# servo_driver_board.net
KiCad netlist of a schematic drawn in EAGLE
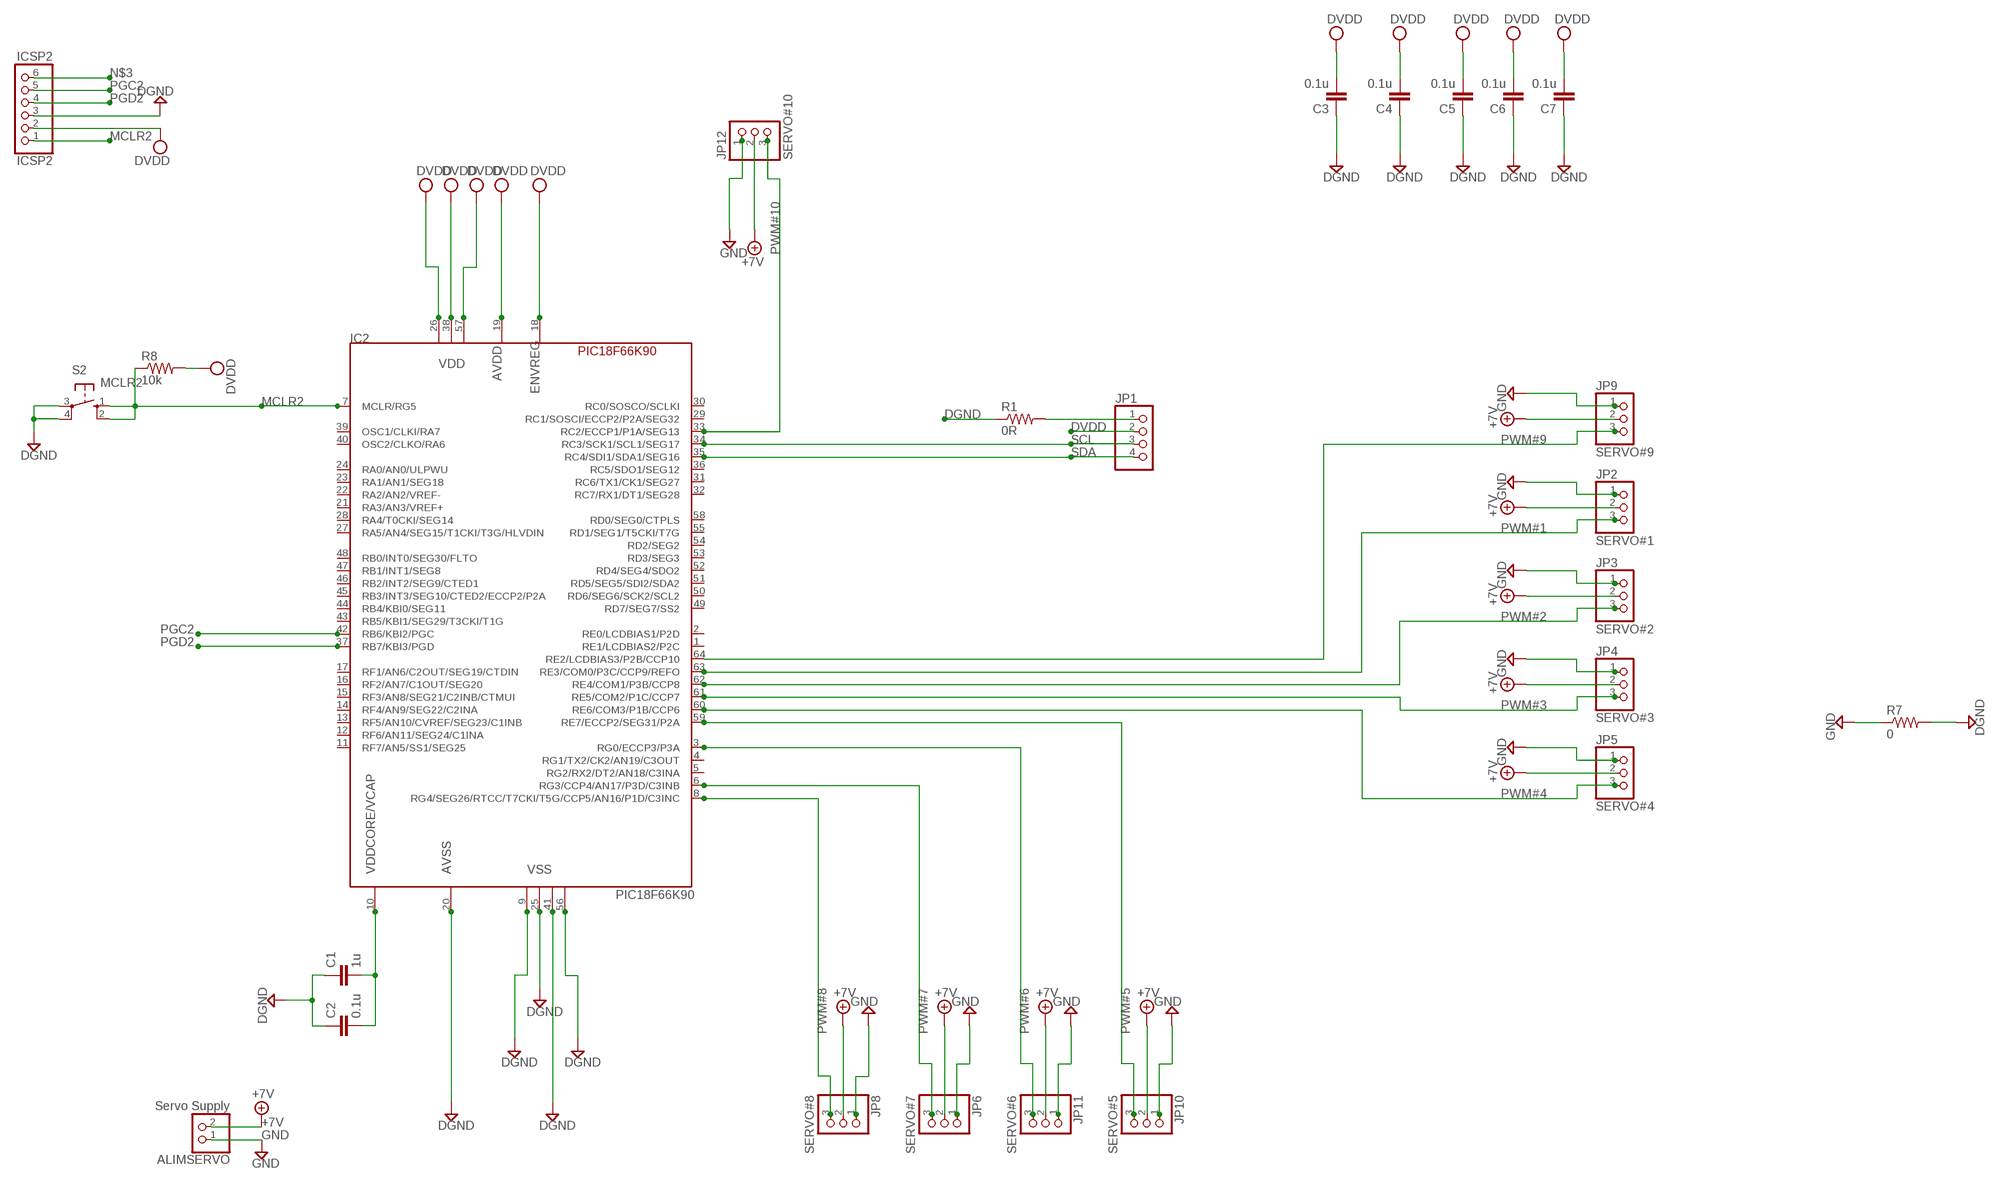
[diagram p0: schematic, sheet 1]

(export (version "E")
  (design (tool "Eeschema 10.0.6"))
  (components
    (comp (ref "ALIMSERVO")
      (value "Servo Supply")
      (footprint "eagle-import:1X02")
      (libsource (lib "eagle-import") (part "PINHD-1X2"))
    )
    (comp (ref "C1")
      (value "1u")
      (footprint "eagle-import:C0805")
      (libsource (lib "eagle-import") (part "C-EUC0805"))
    )
    (comp (ref "C2")
      (value "0.1u")
      (footprint "eagle-import:C0805")
      (libsource (lib "eagle-import") (part "C-EUC0805"))
    )
    (comp (ref "C3")
      (value "0.1u")
      (footprint "eagle-import:C0805")
      (libsource (lib "eagle-import") (part "C-EUC0805"))
    )
    (comp (ref "C4")
      (value "0.1u")
      (footprint "eagle-import:C0805")
      (libsource (lib "eagle-import") (part "C-EUC0805"))
    )
    (comp (ref "C5")
      (value "0.1u")
      (footprint "eagle-import:C0805")
      (libsource (lib "eagle-import") (part "C-EUC0805"))
    )
    (comp (ref "C6")
      (value "0.1u")
      (footprint "eagle-import:C0805")
      (libsource (lib "eagle-import") (part "C-EUC0805"))
    )
    (comp (ref "C7")
      (value "0.1u")
      (footprint "eagle-import:C0805")
      (libsource (lib "eagle-import") (part "C-EUC0805"))
    )
    (comp (ref "IC2")
      (value "PIC18F66K90")
      (footprint "eagle-import:TQFP64-10X10")
      (libsource (lib "eagle-import") (part "PIC18F66K90"))
    )
    (comp (ref "ICSP2")
      (value "ICSP2")
      (footprint "eagle-import:1X06")
      (libsource (lib "eagle-import") (part "PINHD-1X6"))
    )
    (comp (ref "JP1")
      (value "PINHD-1X4/90")
      (footprint "eagle-import:1X04_90")
      (libsource (lib "eagle-import") (part "PINHD-1X4/90"))
    )
    (comp (ref "JP2")
      (value "SERVO#1")
      (footprint "eagle-import:1X03")
      (libsource (lib "eagle-import") (part "PINHD-1X3"))
    )
    (comp (ref "JP3")
      (value "SERVO#2")
      (footprint "eagle-import:1X03")
      (libsource (lib "eagle-import") (part "PINHD-1X3"))
    )
    (comp (ref "JP4")
      (value "SERVO#3")
      (footprint "eagle-import:1X03")
      (libsource (lib "eagle-import") (part "PINHD-1X3"))
    )
    (comp (ref "JP5")
      (value "SERVO#4")
      (footprint "eagle-import:1X03")
      (libsource (lib "eagle-import") (part "PINHD-1X3"))
    )
    (comp (ref "JP6")
      (value "SERVO#7")
      (footprint "eagle-import:1X03")
      (libsource (lib "eagle-import") (part "PINHD-1X3"))
    )
    (comp (ref "JP8")
      (value "SERVO#8")
      (footprint "eagle-import:1X03")
      (libsource (lib "eagle-import") (part "PINHD-1X3"))
    )
    (comp (ref "JP9")
      (value "SERVO#9")
      (footprint "eagle-import:1X03")
      (libsource (lib "eagle-import") (part "PINHD-1X3"))
    )
    (comp (ref "JP10")
      (value "SERVO#5")
      (footprint "eagle-import:1X03")
      (libsource (lib "eagle-import") (part "PINHD-1X3"))
    )
    (comp (ref "JP11")
      (value "SERVO#6")
      (footprint "eagle-import:1X03")
      (libsource (lib "eagle-import") (part "PINHD-1X3"))
    )
    (comp (ref "JP12")
      (value "SERVO#10")
      (footprint "eagle-import:1X03")
      (libsource (lib "eagle-import") (part "PINHD-1X3"))
    )
    (comp (ref "R1")
      (value "0R")
      (footprint "eagle-import:R1206")
      (libsource (lib "eagle-import") (part "R-US_R1206"))
    )
    (comp (ref "R7")
      (value "0")
      (footprint "eagle-import:R1206")
      (libsource (lib "eagle-import") (part "R-US_R1206"))
    )
    (comp (ref "R8")
      (value "10k")
      (footprint "eagle-import:R1206")
      (libsource (lib "eagle-import") (part "R-US_R1206"))
    )
    (comp (ref "S2")
      (value "MCLR2")
      (footprint "eagle-import:B3F-10XX")
      (fields (field (name "MPN") "B3F-1000"))
      (libsource (lib "eagle-import") (part "10-XX"))
    )
  )
  (nets
    (net (code "1") (name "+7V") (class "Default")
      (node (ref "ALIMSERVO") (pin "2") (pinfunction "2_2") (pintype "passive"))
      (node (ref "JP10") (pin "2") (pinfunction "2_2") (pintype "passive"))
      (node (ref "JP11") (pin "2") (pinfunction "2_2") (pintype "passive"))
      (node (ref "JP12") (pin "2") (pinfunction "2_2") (pintype "passive"))
      (node (ref "JP2") (pin "2") (pinfunction "2_2") (pintype "passive"))
      (node (ref "JP3") (pin "2") (pinfunction "2_2") (pintype "passive"))
      (node (ref "JP4") (pin "2") (pinfunction "2_2") (pintype "passive"))
      (node (ref "JP5") (pin "2") (pinfunction "2_2") (pintype "passive"))
      (node (ref "JP6") (pin "2") (pinfunction "2_2") (pintype "passive"))
      (node (ref "JP8") (pin "2") (pinfunction "2_2") (pintype "passive"))
      (node (ref "JP9") (pin "2") (pinfunction "2_2") (pintype "passive"))
    )
    (net (code "2") (name "/MCLR2") (class "Default")
      (node (ref "IC2") (pin "7") (pinfunction "MCLR/RG5_7") (pintype "input"))
      (node (ref "ICSP2") (pin "1") (pinfunction "1_1") (pintype "passive"))
      (node (ref "R8") (pin "1") (pinfunction "1_1") (pintype "passive"))
      (node (ref "S2") (pin "1") (pinfunction "S_1") (pintype "passive"))
      (node (ref "S2") (pin "2") (pinfunction "S1_2") (pintype "passive"))
    )
    (net (code "3") (name "/N$3") (class "Default")
      (node (ref "ICSP2") (pin "6") (pinfunction "6_6") (pintype "passive"))
    )
    (net (code "4") (name "/PGC2") (class "Default")
      (node (ref "IC2") (pin "42") (pinfunction "RB6/KBI2/PGC_42") (pintype "bidirectional"))
      (node (ref "ICSP2") (pin "5") (pinfunction "5_5") (pintype "passive"))
    )
    (net (code "5") (name "/PGD2") (class "Default")
      (node (ref "IC2") (pin "37") (pinfunction "RB7/KBI3/PGD_37") (pintype "bidirectional"))
      (node (ref "ICSP2") (pin "4") (pinfunction "4_4") (pintype "passive"))
    )
    (net (code "6") (name "/SCL") (class "Default")
      (node (ref "IC2") (pin "34") (pinfunction "RC3/SCK1/SCL1/SEG17_34") (pintype "bidirectional"))
      (node (ref "JP1") (pin "3") (pinfunction "3_3") (pintype "passive"))
    )
    (net (code "7") (name "/SDA") (class "Default")
      (node (ref "IC2") (pin "35") (pinfunction "RC4/SDI1/SDA1/SEG16_35") (pintype "bidirectional"))
      (node (ref "JP1") (pin "4") (pinfunction "4_4") (pintype "passive"))
    )
    (net (code "8") (name "DGND") (class "Default")
      (node (ref "C1") (pin "1") (pinfunction "1_1") (pintype "passive"))
      (node (ref "C2") (pin "1") (pinfunction "1_1") (pintype "passive"))
      (node (ref "C3") (pin "1") (pinfunction "1_1") (pintype "passive"))
      (node (ref "C4") (pin "1") (pinfunction "1_1") (pintype "passive"))
      (node (ref "C5") (pin "1") (pinfunction "1_1") (pintype "passive"))
      (node (ref "C6") (pin "1") (pinfunction "1_1") (pintype "passive"))
      (node (ref "C7") (pin "1") (pinfunction "1_1") (pintype "passive"))
      (node (ref "IC2") (pin "20") (pinfunction "AVSS_20") (pintype "power_in"))
      (node (ref "IC2") (pin "25") (pinfunction "VSS_25") (pintype "power_in"))
      (node (ref "IC2") (pin "41") (pinfunction "VSS_41") (pintype "power_in"))
      (node (ref "IC2") (pin "56") (pinfunction "VSS_56") (pintype "power_in"))
      (node (ref "IC2") (pin "9") (pinfunction "VSS_9") (pintype "power_in"))
      (node (ref "ICSP2") (pin "3") (pinfunction "3_3") (pintype "passive"))
      (node (ref "R1") (pin "1") (pinfunction "1_1") (pintype "passive"))
      (node (ref "R7") (pin "2") (pinfunction "2_2") (pintype "passive"))
      (node (ref "S2") (pin "3") (pinfunction "P_3") (pintype "passive"))
      (node (ref "S2") (pin "4") (pinfunction "P1_4") (pintype "passive"))
    )
    (net (code "9") (name "DVDD") (class "Default")
      (node (ref "C3") (pin "2") (pinfunction "2_2") (pintype "passive"))
      (node (ref "C4") (pin "2") (pinfunction "2_2") (pintype "passive"))
      (node (ref "C5") (pin "2") (pinfunction "2_2") (pintype "passive"))
      (node (ref "C6") (pin "2") (pinfunction "2_2") (pintype "passive"))
      (node (ref "C7") (pin "2") (pinfunction "2_2") (pintype "passive"))
      (node (ref "IC2") (pin "18") (pinfunction "ENVREG_18") (pintype "power_in"))
      (node (ref "IC2") (pin "19") (pinfunction "AVDD_19") (pintype "power_in"))
      (node (ref "IC2") (pin "26") (pinfunction "VDD_26") (pintype "power_in"))
      (node (ref "IC2") (pin "38") (pinfunction "VDD_38") (pintype "power_in"))
      (node (ref "IC2") (pin "57") (pinfunction "VDD_57") (pintype "power_in"))
      (node (ref "ICSP2") (pin "2") (pinfunction "2_2") (pintype "passive"))
      (node (ref "JP1") (pin "2") (pinfunction "2_2") (pintype "passive"))
      (node (ref "R8") (pin "2") (pinfunction "2_2") (pintype "passive"))
    )
    (net (code "10") (name "GND") (class "Default")
      (node (ref "ALIMSERVO") (pin "1") (pinfunction "1_1") (pintype "passive"))
      (node (ref "JP10") (pin "1") (pinfunction "1_1") (pintype "passive"))
      (node (ref "JP11") (pin "1") (pinfunction "1_1") (pintype "passive"))
      (node (ref "JP12") (pin "1") (pinfunction "1_1") (pintype "passive"))
      (node (ref "JP2") (pin "1") (pinfunction "1_1") (pintype "passive"))
      (node (ref "JP3") (pin "1") (pinfunction "1_1") (pintype "passive"))
      (node (ref "JP4") (pin "1") (pinfunction "1_1") (pintype "passive"))
      (node (ref "JP5") (pin "1") (pinfunction "1_1") (pintype "passive"))
      (node (ref "JP6") (pin "1") (pinfunction "1_1") (pintype "passive"))
      (node (ref "JP8") (pin "1") (pinfunction "1_1") (pintype "passive"))
      (node (ref "JP9") (pin "1") (pinfunction "1_1") (pintype "passive"))
      (node (ref "R7") (pin "1") (pinfunction "1_1") (pintype "passive"))
    )
    (net (code "11") (name "Net-(IC2-RC2{slash}ECCP1{slash}P1A{slash}SEG13)") (class "Default")
      (node (ref "IC2") (pin "33") (pinfunction "RC2/ECCP1/P1A/SEG13_33") (pintype "bidirectional"))
      (node (ref "JP12") (pin "3") (pinfunction "3_3") (pintype "passive"))
    )
    (net (code "12") (name "Net-(IC2-RE2{slash}LCDBIAS3{slash}P2B{slash}CCP10)") (class "Default")
      (node (ref "IC2") (pin "64") (pinfunction "RE2/LCDBIAS3/P2B/CCP10_64") (pintype "bidirectional"))
      (node (ref "JP9") (pin "3") (pinfunction "3_3") (pintype "passive"))
    )
    (net (code "13") (name "Net-(IC2-RE3{slash}COM0{slash}P3C{slash}CCP9{slash}REFO)") (class "Default")
      (node (ref "IC2") (pin "63") (pinfunction "RE3/COM0/P3C/CCP9/REFO_63") (pintype "bidirectional"))
      (node (ref "JP2") (pin "3") (pinfunction "3_3") (pintype "passive"))
    )
    (net (code "14") (name "Net-(IC2-RE4{slash}COM1{slash}P3B{slash}CCP8)") (class "Default")
      (node (ref "IC2") (pin "62") (pinfunction "RE4/COM1/P3B/CCP8_62") (pintype "bidirectional"))
      (node (ref "JP3") (pin "3") (pinfunction "3_3") (pintype "passive"))
    )
    (net (code "15") (name "Net-(IC2-RE5{slash}COM2{slash}P1C{slash}CCP7)") (class "Default")
      (node (ref "IC2") (pin "61") (pinfunction "RE5/COM2/P1C/CCP7_61") (pintype "bidirectional"))
      (node (ref "JP4") (pin "3") (pinfunction "3_3") (pintype "passive"))
    )
    (net (code "16") (name "Net-(IC2-RE6{slash}COM3{slash}P1B{slash}CCP6)") (class "Default")
      (node (ref "IC2") (pin "60") (pinfunction "RE6/COM3/P1B/CCP6_60") (pintype "bidirectional"))
      (node (ref "JP5") (pin "3") (pinfunction "3_3") (pintype "passive"))
    )
    (net (code "17") (name "Net-(IC2-RE7{slash}ECCP2{slash}SEG31{slash}P2A)") (class "Default")
      (node (ref "IC2") (pin "59") (pinfunction "RE7/ECCP2/SEG31/P2A_59") (pintype "bidirectional"))
      (node (ref "JP10") (pin "3") (pinfunction "3_3") (pintype "passive"))
    )
    (net (code "18") (name "Net-(IC2-RG0{slash}ECCP3{slash}P3A)") (class "Default")
      (node (ref "IC2") (pin "3") (pinfunction "RG0/ECCP3/P3A_3") (pintype "bidirectional"))
      (node (ref "JP11") (pin "3") (pinfunction "3_3") (pintype "passive"))
    )
    (net (code "19") (name "Net-(IC2-RG3{slash}CCP4{slash}AN17{slash}P3D{slash}C3INB)") (class "Default")
      (node (ref "IC2") (pin "6") (pinfunction "RG3/CCP4/AN17/P3D/C3INB_6") (pintype "bidirectional"))
      (node (ref "JP6") (pin "3") (pinfunction "3_3") (pintype "passive"))
    )
    (net (code "20") (name "Net-(IC2-RG4{slash}SEG26{slash}RTCC{slash}T7CKI{slash}T5G{slash}CCP5{slash}AN16{slash}P1D{slash}C3INC)") (class "Default")
      (node (ref "IC2") (pin "8") (pinfunction "RG4/SEG26/RTCC/T7CKI/T5G/CCP5/AN16/P1D/C3INC_8") (pintype "bidirectional"))
      (node (ref "JP8") (pin "3") (pinfunction "3_3") (pintype "passive"))
    )
    (net (code "21") (name "Net-(IC2-VDDCORE{slash}VCAP)") (class "Default")
      (node (ref "C1") (pin "2") (pinfunction "2_2") (pintype "passive"))
      (node (ref "C2") (pin "2") (pinfunction "2_2") (pintype "passive"))
      (node (ref "IC2") (pin "10") (pinfunction "VDDCORE/VCAP_10") (pintype "power_in"))
    )
    (net (code "22") (name "Net-(JP1-Pad1)") (class "Default")
      (node (ref "JP1") (pin "1") (pinfunction "1_1") (pintype "passive"))
      (node (ref "R1") (pin "2") (pinfunction "2_2") (pintype "passive"))
    )
    (net (code "23") (name "unconnected-(IC2-OSC1{slash}CLKI{slash}RA7-Pad39)") (class "Default")
      (node (ref "IC2") (pin "39") (pinfunction "OSC1/CLKI/RA7_39") (pintype "bidirectional"))
    )
    (net (code "24") (name "unconnected-(IC2-OSC2{slash}CLKO{slash}RA6-Pad40)") (class "Default")
      (node (ref "IC2") (pin "40") (pinfunction "OSC2/CLKO/RA6_40") (pintype "bidirectional"))
    )
    (net (code "25") (name "unconnected-(IC2-RA0{slash}AN0{slash}ULPWU-Pad24)") (class "Default")
      (node (ref "IC2") (pin "24") (pinfunction "RA0/AN0/ULPWU_24") (pintype "bidirectional"))
    )
    (net (code "26") (name "unconnected-(IC2-RA1{slash}AN1{slash}SEG18-Pad23)") (class "Default")
      (node (ref "IC2") (pin "23") (pinfunction "RA1/AN1/SEG18_23") (pintype "bidirectional"))
    )
    (net (code "27") (name "unconnected-(IC2-RA2{slash}AN2{slash}VREF--Pad22)") (class "Default")
      (node (ref "IC2") (pin "22") (pinfunction "RA2/AN2/VREF-_22") (pintype "bidirectional"))
    )
    (net (code "28") (name "unconnected-(IC2-RA3{slash}AN3{slash}VREF+-Pad21)") (class "Default")
      (node (ref "IC2") (pin "21") (pinfunction "RA3/AN3/VREF+_21") (pintype "bidirectional"))
    )
    (net (code "29") (name "unconnected-(IC2-RA4{slash}T0CKI{slash}SEG14-Pad28)") (class "Default")
      (node (ref "IC2") (pin "28") (pinfunction "RA4/T0CKI/SEG14_28") (pintype "bidirectional"))
    )
    (net (code "30") (name "unconnected-(IC2-RA5{slash}AN4{slash}SEG15{slash}T1CKI{slash}T3G{slash}HLVDIN-Pad27)") (class "Default")
      (node (ref "IC2") (pin "27") (pinfunction "RA5/AN4/SEG15/T1CKI/T3G/HLVDIN_27") (pintype "bidirectional"))
    )
    (net (code "31") (name "unconnected-(IC2-RB0{slash}INT0{slash}SEG30{slash}FLTO-Pad48)") (class "Default")
      (node (ref "IC2") (pin "48") (pinfunction "RB0/INT0/SEG30/FLTO_48") (pintype "bidirectional"))
    )
    (net (code "32") (name "unconnected-(IC2-RB1{slash}INT1{slash}SEG8-Pad47)") (class "Default")
      (node (ref "IC2") (pin "47") (pinfunction "RB1/INT1/SEG8_47") (pintype "bidirectional"))
    )
    (net (code "33") (name "unconnected-(IC2-RB2{slash}INT2{slash}SEG9{slash}CTED1-Pad46)") (class "Default")
      (node (ref "IC2") (pin "46") (pinfunction "RB2/INT2/SEG9/CTED1_46") (pintype "bidirectional"))
    )
    (net (code "34") (name "unconnected-(IC2-RB3{slash}INT3{slash}SEG10{slash}CTED2{slash}ECCP2{slash}P2A-Pad45)") (class "Default")
      (node (ref "IC2") (pin "45") (pinfunction "RB3/INT3/SEG10/CTED2/ECCP2/P2A_45") (pintype "bidirectional"))
    )
    (net (code "35") (name "unconnected-(IC2-RB4{slash}KBI0{slash}SEG11-Pad44)") (class "Default")
      (node (ref "IC2") (pin "44") (pinfunction "RB4/KBI0/SEG11_44") (pintype "bidirectional"))
    )
    (net (code "36") (name "unconnected-(IC2-RB5{slash}KBI1{slash}SEG29{slash}T3CKI{slash}T1G-Pad43)") (class "Default")
      (node (ref "IC2") (pin "43") (pinfunction "RB5/KBI1/SEG29/T3CKI/T1G_43") (pintype "bidirectional"))
    )
    (net (code "37") (name "unconnected-(IC2-RC0{slash}SOSCO{slash}SCLKI-Pad30)") (class "Default")
      (node (ref "IC2") (pin "30") (pinfunction "RC0/SOSCO/SCLKI_30") (pintype "bidirectional"))
    )
    (net (code "38") (name "unconnected-(IC2-RC1{slash}SOSCI{slash}ECCP2{slash}P2A{slash}SEG32-Pad29)") (class "Default")
      (node (ref "IC2") (pin "29") (pinfunction "RC1/SOSCI/ECCP2/P2A/SEG32_29") (pintype "bidirectional"))
    )
    (net (code "39") (name "unconnected-(IC2-RC5{slash}SDO1{slash}SEG12-Pad36)") (class "Default")
      (node (ref "IC2") (pin "36") (pinfunction "RC5/SDO1/SEG12_36") (pintype "bidirectional"))
    )
    (net (code "40") (name "unconnected-(IC2-RC6{slash}TX1{slash}CK1{slash}SEG27-Pad31)") (class "Default")
      (node (ref "IC2") (pin "31") (pinfunction "RC6/TX1/CK1/SEG27_31") (pintype "bidirectional"))
    )
    (net (code "41") (name "unconnected-(IC2-RC7{slash}RX1{slash}DT1{slash}SEG28-Pad32)") (class "Default")
      (node (ref "IC2") (pin "32") (pinfunction "RC7/RX1/DT1/SEG28_32") (pintype "bidirectional"))
    )
    (net (code "42") (name "unconnected-(IC2-RD0{slash}SEG0{slash}CTPLS-Pad58)") (class "Default")
      (node (ref "IC2") (pin "58") (pinfunction "RD0/SEG0/CTPLS_58") (pintype "bidirectional"))
    )
    (net (code "43") (name "unconnected-(IC2-RD1{slash}SEG1{slash}T5CKI{slash}T7G-Pad55)") (class "Default")
      (node (ref "IC2") (pin "55") (pinfunction "RD1/SEG1/T5CKI/T7G_55") (pintype "bidirectional"))
    )
    (net (code "44") (name "unconnected-(IC2-RD2{slash}SEG2-Pad54)") (class "Default")
      (node (ref "IC2") (pin "54") (pinfunction "RD2/SEG2_54") (pintype "bidirectional"))
    )
    (net (code "45") (name "unconnected-(IC2-RD3{slash}SEG3-Pad53)") (class "Default")
      (node (ref "IC2") (pin "53") (pinfunction "RD3/SEG3_53") (pintype "bidirectional"))
    )
    (net (code "46") (name "unconnected-(IC2-RD4{slash}SEG4{slash}SDO2-Pad52)") (class "Default")
      (node (ref "IC2") (pin "52") (pinfunction "RD4/SEG4/SDO2_52") (pintype "bidirectional"))
    )
    (net (code "47") (name "unconnected-(IC2-RD5{slash}SEG5{slash}SDI2{slash}SDA2-Pad51)") (class "Default")
      (node (ref "IC2") (pin "51") (pinfunction "RD5/SEG5/SDI2/SDA2_51") (pintype "bidirectional"))
    )
    (net (code "48") (name "unconnected-(IC2-RD6{slash}SEG6{slash}SCK2{slash}SCL2-Pad50)") (class "Default")
      (node (ref "IC2") (pin "50") (pinfunction "RD6/SEG6/SCK2/SCL2_50") (pintype "bidirectional"))
    )
    (net (code "49") (name "unconnected-(IC2-RD7{slash}SEG7{slash}SS2-Pad49)") (class "Default")
      (node (ref "IC2") (pin "49") (pinfunction "RD7/SEG7/SS2_49") (pintype "bidirectional"))
    )
    (net (code "50") (name "unconnected-(IC2-RE0{slash}LCDBIAS1{slash}P2D-Pad2)") (class "Default")
      (node (ref "IC2") (pin "2") (pinfunction "RE0/LCDBIAS1/P2D_2") (pintype "bidirectional"))
    )
    (net (code "51") (name "unconnected-(IC2-RE1{slash}LCDBIAS2{slash}P2C-Pad1)") (class "Default")
      (node (ref "IC2") (pin "1") (pinfunction "RE1/LCDBIAS2/P2C_1") (pintype "bidirectional"))
    )
    (net (code "52") (name "unconnected-(IC2-RF1{slash}AN6{slash}C2OUT{slash}SEG19{slash}CTDIN-Pad17)") (class "Default")
      (node (ref "IC2") (pin "17") (pinfunction "RF1/AN6/C2OUT/SEG19/CTDIN_17") (pintype "bidirectional"))
    )
    (net (code "53") (name "unconnected-(IC2-RF2{slash}AN7{slash}C1OUT{slash}SEG20-Pad16)") (class "Default")
      (node (ref "IC2") (pin "16") (pinfunction "RF2/AN7/C1OUT/SEG20_16") (pintype "bidirectional"))
    )
    (net (code "54") (name "unconnected-(IC2-RF3{slash}AN8{slash}SEG21{slash}C2INB{slash}CTMUI-Pad15)") (class "Default")
      (node (ref "IC2") (pin "15") (pinfunction "RF3/AN8/SEG21/C2INB/CTMUI_15") (pintype "bidirectional"))
    )
    (net (code "55") (name "unconnected-(IC2-RF4{slash}AN9{slash}SEG22{slash}C2INA-Pad14)") (class "Default")
      (node (ref "IC2") (pin "14") (pinfunction "RF4/AN9/SEG22/C2INA_14") (pintype "bidirectional"))
    )
    (net (code "56") (name "unconnected-(IC2-RF5{slash}AN10{slash}CVREF{slash}SEG23{slash}C1INB-Pad13)") (class "Default")
      (node (ref "IC2") (pin "13") (pinfunction "RF5/AN10/CVREF/SEG23/C1INB_13") (pintype "bidirectional"))
    )
    (net (code "57") (name "unconnected-(IC2-RF6{slash}AN11{slash}SEG24{slash}C1INA-Pad12)") (class "Default")
      (node (ref "IC2") (pin "12") (pinfunction "RF6/AN11/SEG24/C1INA_12") (pintype "bidirectional"))
    )
    (net (code "58") (name "unconnected-(IC2-RF7{slash}AN5{slash}SS1{slash}SEG25-Pad11)") (class "Default")
      (node (ref "IC2") (pin "11") (pinfunction "RF7/AN5/SS1/SEG25_11") (pintype "bidirectional"))
    )
    (net (code "59") (name "unconnected-(IC2-RG1{slash}TX2{slash}CK2{slash}AN19{slash}C3OUT-Pad4)") (class "Default")
      (node (ref "IC2") (pin "4") (pinfunction "RG1/TX2/CK2/AN19/C3OUT_4") (pintype "bidirectional"))
    )
    (net (code "60") (name "unconnected-(IC2-RG2{slash}RX2{slash}DT2{slash}AN18{slash}C3INA-Pad5)") (class "Default")
      (node (ref "IC2") (pin "5") (pinfunction "RG2/RX2/DT2/AN18/C3INA_5") (pintype "bidirectional"))
    )
  )
)
